# Switch.net
KiCad netlist of a schematic drawn in Altium Designer
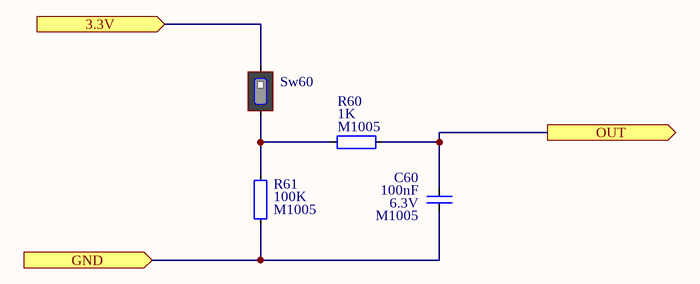
[diagram p0: Switch.SchDoc]

(export (version "E")
  (design (tool "Eeschema 10.0.6"))
  (components
    (comp (ref "C60")
      (value "100nF")
      (footprint "Capacitor_Ceramic_M1005_I0402")
      (description "Cap, Cer, 100nF, 6.3V, M1005")
      (fields
        (field (name "VOLTAGE") "6.3V")
        (field (name "MANUFACTURER PART NUMBER") "04026D104KAT4A")
        (field (name "MANUFACTURER") "Kyocera")
        (field (name "PACKAGE") "M1005")
      )
      (libsource (lib "Capacitor") (part "Capacitor_Ceramic"))
    )
    (comp (ref "R60")
      (value "1K")
      (footprint "Resistor_Smd_M1005_I0402")
      (description "Res, 1K, 1%, M1005")
      (fields
        (field (name "TOLERANCE") "1%")
        (field (name "MANUFACTURER") "Yageo")
        (field (name "PACKAGE") "M1005")
      )
      (libsource (lib "Resistor") (part "Resistor"))
    )
    (comp (ref "R61")
      (value "100K")
      (footprint "Resistor_Smd_M1005_I0402")
      (description "Res, 100K, 1%, M1005")
      (fields
        (field (name "TOLERANCE") "1%")
        (field (name "MANUFACTURER") "Yageo")
        (field (name "PACKAGE") "M1005")
      )
      (libsource (lib "Resistor") (part "Resistor"))
    )
    (comp (ref "Sw60")
      (value "Slide, SPST")
      (footprint "Slide, SPST - C&K, SDA01HxS")
      (libsource (lib "Switch") (part "Slide, SPST"))
    )
  )
  (nets
    (net (code "1") (name "/3.3V") (class "Default")
      (node (ref "Sw60") (pin "A") (pinfunction "A_A") (pintype "passive"))
    )
    (net (code "2") (name "/GND") (class "Default")
      (node (ref "C60") (pin "2") (pinfunction "2_2") (pintype "passive"))
      (node (ref "R61") (pin "2") (pinfunction "2_2") (pintype "passive"))
    )
    (net (code "3") (name "/OUT") (class "Default")
      (node (ref "C60") (pin "1") (pinfunction "1_1") (pintype "passive"))
      (node (ref "R60") (pin "2") (pinfunction "2_2") (pintype "passive"))
    )
    (net (code "4") (name "Net-(R60-Pad1)") (class "Default")
      (node (ref "R60") (pin "1") (pinfunction "1_1") (pintype "passive"))
      (node (ref "R61") (pin "1") (pinfunction "1_1") (pintype "passive"))
      (node (ref "Sw60") (pin "B") (pinfunction "B_B") (pintype "passive"))
    )
  )
)
